# stateindicator.net
KiCad netlist of a schematic drawn in EAGLE
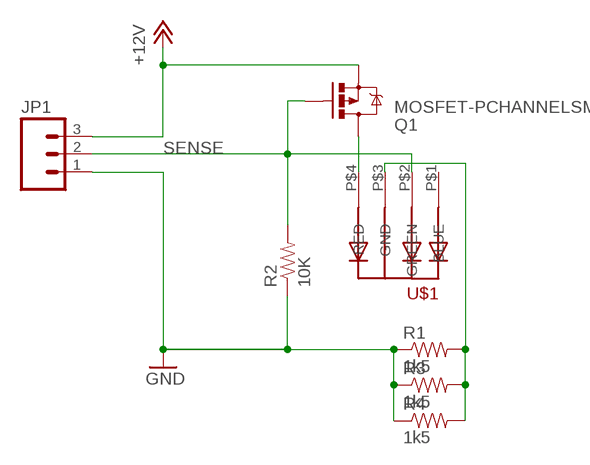
[diagram p0: schematic, sheet 1]

(export (version "E")
  (design (tool "Eeschema 10.0.6"))
  (components
    (comp (ref "JP1")
      (value "M03POLAR_LOCK")
      (footprint "eagle-import:MOLEX-1X3_LOCK")
      (libsource (lib "eagle-import") (part "M03POLAR_LOCK"))
    )
    (comp (ref "Q1")
      (value "MOSFET-PCHANNELSMD")
      (footprint "eagle-import:SOT23-3")
      (libsource (lib "eagle-import") (part "MOSFET-PCHANNELSMD"))
    )
    (comp (ref "R1")
      (value "1k5")
      (footprint "eagle-import:0603-RES")
      (libsource (lib "eagle-import") (part "RESISTOR0603-RES"))
    )
    (comp (ref "R2")
      (value "10K")
      (footprint "eagle-import:0603-RES")
      (libsource (lib "eagle-import") (part "RESISTOR0603-RES"))
    )
    (comp (ref "R3")
      (value "1k5")
      (footprint "eagle-import:0603-RES")
      (libsource (lib "eagle-import") (part "RESISTOR0603-RES"))
    )
    (comp (ref "R4")
      (value "1k5")
      (footprint "eagle-import:0603-RES")
      (libsource (lib "eagle-import") (part "RESISTOR0603-RES"))
    )
    (comp (ref "U$1")
      (value "5MMRGBLED")
      (footprint "eagle-import:LED5MMRGB")
      (libsource (lib "eagle-import") (part "5MMRGBLED"))
    )
  )
  (nets
    (net (code "1") (name "+12V") (class "Default")
      (node (ref "JP1") (pin "3") (pinfunction "3_3") (pintype "passive"))
      (node (ref "Q1") (pin "2") (pinfunction "S_2") (pintype "passive"))
    )
    (net (code "2") (name "/SENSE") (class "Default")
      (node (ref "JP1") (pin "2") (pinfunction "2_2") (pintype "passive"))
      (node (ref "Q1") (pin "1") (pinfunction "G_1") (pintype "passive"))
      (node (ref "R2") (pin "2") (pinfunction "2_2") (pintype "passive"))
      (node (ref "U$1") (pin "P$2") (pinfunction "GREEN_P$2") (pintype "bidirectional"))
    )
    (net (code "3") (name "GND") (class "Default")
      (node (ref "JP1") (pin "1") (pinfunction "1_1") (pintype "passive"))
      (node (ref "R1") (pin "1") (pinfunction "1_1") (pintype "passive"))
      (node (ref "R2") (pin "1") (pinfunction "1_1") (pintype "passive"))
      (node (ref "R3") (pin "1") (pinfunction "1_1") (pintype "passive"))
      (node (ref "R4") (pin "1") (pinfunction "1_1") (pintype "passive"))
    )
    (net (code "4") (name "Net-(Q1-D)") (class "Default")
      (node (ref "Q1") (pin "3") (pinfunction "D_3") (pintype "passive"))
      (node (ref "U$1") (pin "P$4") (pinfunction "RED_P$4") (pintype "bidirectional"))
    )
    (net (code "5") (name "Net-(U$1-GND)") (class "Default")
      (node (ref "R1") (pin "2") (pinfunction "2_2") (pintype "passive"))
      (node (ref "R3") (pin "2") (pinfunction "2_2") (pintype "passive"))
      (node (ref "R4") (pin "2") (pinfunction "2_2") (pintype "passive"))
      (node (ref "U$1") (pin "P$3") (pinfunction "GND_P$3") (pintype "bidirectional"))
    )
    (net (code "6") (name "unconnected-(U$1-BLUE-PadP$1)") (class "Default")
      (node (ref "U$1") (pin "P$1") (pinfunction "BLUE_P$1") (pintype "bidirectional"))
    )
  )
)
